# Leds.net
KiCad netlist of a schematic drawn in Altium Designer
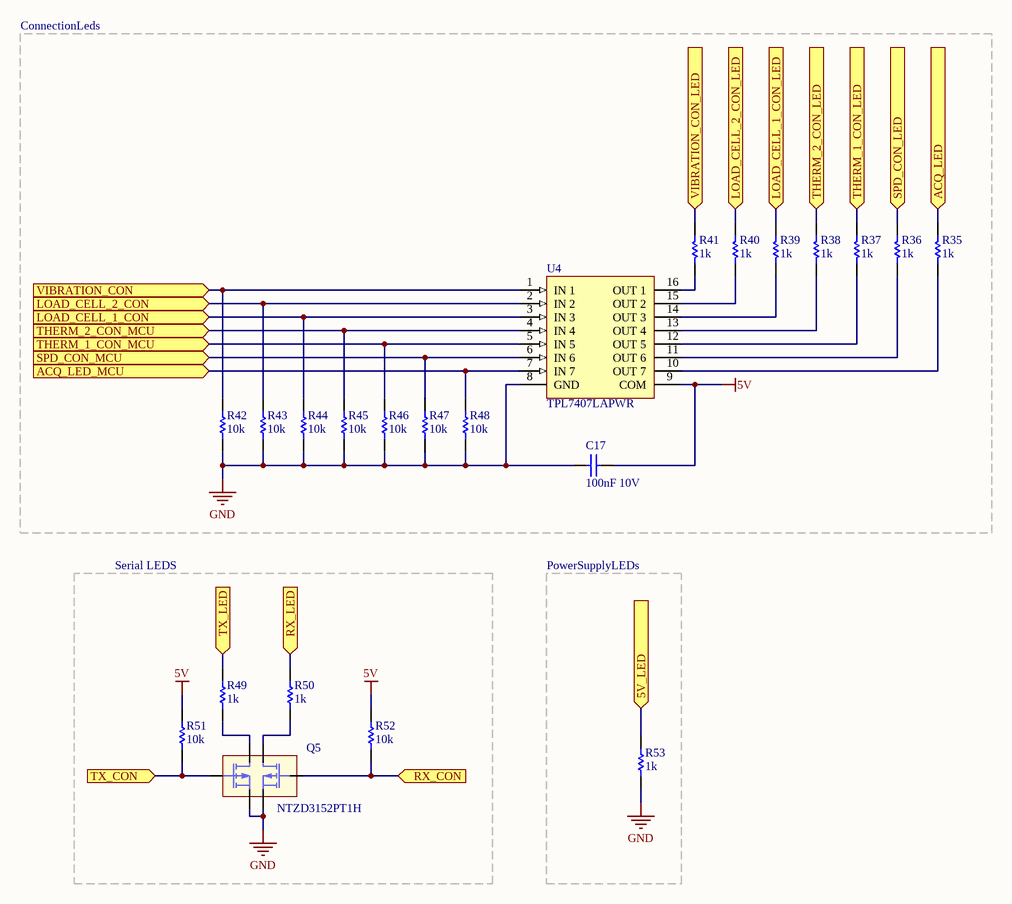
[diagram p0: Leds.SchDoc]

(export (version "E")
  (design (tool "Eeschema 10.0.6"))
  (components
    (comp (ref "C17")
      (value "100nF 10V")
      (footprint "0402")
      (description "Capacitor")
      (fields (field (name "PARTNUMBER") "CAP.100n.10V.20%.SMD.0402") (field (name "MANUFACTURER") "Wurth"))
      (libsource (lib "IntLib") (part "Cap"))
    )
    (comp (ref "Q5")
      (value "NTZD3152PT1H")
      (footprint "SOT23-6_M")
      (description "−20 V, −430 mA, Dual P−Channel with ESD Protection, SOT−563")
      (fields (field (name "PARTNUMBER") "NTZD315PT1H") (field (name "MANUFACTURER") "ON Semiconductor"))
      (libsource (lib "IntLib") (part "NTZD3152PT1H"))
    )
    (comp (ref "R35")
      (value "1k")
      (footprint "6-0805_M")
      (description "Resistor")
      (fields (field (name "PARTNUMBER") "RES.1K.1/8W.5%.SMD.0805") (field (name "MANUFACTURER") "Yageo"))
      (libsource (lib "IntLib") (part "Res"))
    )
    (comp (ref "R36")
      (value "1k")
      (footprint "6-0805_M")
      (description "Resistor")
      (fields (field (name "PARTNUMBER") "RES.1K.1/8W.5%.SMD.0805") (field (name "MANUFACTURER") "Yageo"))
      (libsource (lib "IntLib") (part "Res"))
    )
    (comp (ref "R37")
      (value "1k")
      (footprint "6-0805_M")
      (description "Resistor")
      (fields (field (name "PARTNUMBER") "RES.1K.1/8W.5%.SMD.0805") (field (name "MANUFACTURER") "Yageo"))
      (libsource (lib "IntLib") (part "Res"))
    )
    (comp (ref "R38")
      (value "1k")
      (footprint "6-0805_M")
      (description "Resistor")
      (fields (field (name "PARTNUMBER") "RES.1K.1/8W.5%.SMD.0805") (field (name "MANUFACTURER") "Yageo"))
      (libsource (lib "IntLib") (part "Res"))
    )
    (comp (ref "R39")
      (value "1k")
      (footprint "6-0805_M")
      (description "Resistor")
      (fields (field (name "PARTNUMBER") "RES.1K.1/8W.5%.SMD.0805") (field (name "MANUFACTURER") "Yageo"))
      (libsource (lib "IntLib") (part "Res"))
    )
    (comp (ref "R40")
      (value "1k")
      (footprint "6-0805_M")
      (description "Resistor")
      (fields (field (name "PARTNUMBER") "RES.1K.1/8W.5%.SMD.0805") (field (name "MANUFACTURER") "Yageo"))
      (libsource (lib "IntLib") (part "Res"))
    )
    (comp (ref "R41")
      (value "1k")
      (footprint "6-0805_M")
      (description "Resistor")
      (fields (field (name "PARTNUMBER") "RES.1K.1/8W.5%.SMD.0805") (field (name "MANUFACTURER") "Yageo"))
      (libsource (lib "IntLib") (part "Res"))
    )
    (comp (ref "R42")
      (value "10k")
      (footprint "6-0805_M")
      (description "Resistor")
      (fields (field (name "PARTNUMBER") "RES.10K.1/8W.5%.SMD.0805") (field (name "MANUFACTURER") "Yageo"))
      (libsource (lib "IntLib") (part "Res"))
    )
    (comp (ref "R43")
      (value "10k")
      (footprint "6-0805_M")
      (description "Resistor")
      (fields (field (name "PARTNUMBER") "RES.10K.1/8W.5%.SMD.0805") (field (name "MANUFACTURER") "Yageo"))
      (libsource (lib "IntLib") (part "Res"))
    )
    (comp (ref "R44")
      (value "10k")
      (footprint "6-0805_M")
      (description "Resistor")
      (fields (field (name "PARTNUMBER") "RES.10K.1/8W.5%.SMD.0805") (field (name "MANUFACTURER") "Yageo"))
      (libsource (lib "IntLib") (part "Res"))
    )
    (comp (ref "R45")
      (value "10k")
      (footprint "6-0805_M")
      (description "Resistor")
      (fields (field (name "PARTNUMBER") "RES.10K.1/8W.5%.SMD.0805") (field (name "MANUFACTURER") "Yageo"))
      (libsource (lib "IntLib") (part "Res"))
    )
    (comp (ref "R46")
      (value "10k")
      (footprint "6-0805_M")
      (description "Resistor")
      (fields (field (name "PARTNUMBER") "RES.10K.1/8W.5%.SMD.0805") (field (name "MANUFACTURER") "Yageo"))
      (libsource (lib "IntLib") (part "Res"))
    )
    (comp (ref "R47")
      (value "10k")
      (footprint "6-0805_M")
      (description "Resistor")
      (fields (field (name "PARTNUMBER") "RES.10K.1/8W.5%.SMD.0805") (field (name "MANUFACTURER") "Yageo"))
      (libsource (lib "IntLib") (part "Res"))
    )
    (comp (ref "R48")
      (value "10k")
      (footprint "6-0805_M")
      (description "Resistor")
      (fields (field (name "PARTNUMBER") "RES.10K.1/8W.5%.SMD.0805") (field (name "MANUFACTURER") "Yageo"))
      (libsource (lib "IntLib") (part "Res"))
    )
    (comp (ref "R49")
      (value "1k")
      (footprint "6-0805_M")
      (description "Resistor")
      (fields (field (name "PARTNUMBER") "RES.1K.1/8W.5%.SMD.0805") (field (name "MANUFACTURER") "Yageo"))
      (libsource (lib "IntLib") (part "Res"))
    )
    (comp (ref "R50")
      (value "1k")
      (footprint "6-0805_M")
      (description "Resistor")
      (fields (field (name "PARTNUMBER") "RES.1K.1/8W.5%.SMD.0805") (field (name "MANUFACTURER") "Yageo"))
      (libsource (lib "IntLib") (part "Res"))
    )
    (comp (ref "R51")
      (value "10k")
      (footprint "6-0805_M")
      (description "Resistor")
      (fields (field (name "PARTNUMBER") "RES.10K.1/8W.5%.SMD.0805") (field (name "MANUFACTURER") "Yageo"))
      (libsource (lib "IntLib") (part "Res"))
    )
    (comp (ref "R52")
      (value "10k")
      (footprint "6-0805_M")
      (description "Resistor")
      (fields (field (name "PARTNUMBER") "RES.10K.1/8W.5%.SMD.0805") (field (name "MANUFACTURER") "Yageo"))
      (libsource (lib "IntLib") (part "Res"))
    )
    (comp (ref "R53")
      (value "1k")
      (footprint "6-0805_M")
      (description "Resistor")
      (fields (field (name "PARTNUMBER") "RES.1K.1/8W.5%.SMD.0805") (field (name "MANUFACTURER") "Yageo"))
      (libsource (lib "IntLib") (part "Res"))
    )
    (comp (ref "U4")
      (value "TPL7407LAPWR")
      (footprint "TSOP-16")
      (fields (field (name "MANUFACTURER") "TL2575-05"))
      (libsource (lib "IntLib") (part "TPL7407LAPWR"))
    )
  )
  (nets
    (net (code "1") (name "/5V_LED") (class "Default")
      (node (ref "R53") (pin "2") (pinfunction "2_2") (pintype "passive"))
    )
    (net (code "2") (name "/ACQ_LED") (class "Default")
      (node (ref "R35") (pin "2") (pinfunction "2_2") (pintype "passive"))
    )
    (net (code "3") (name "/ACQ_LED_MCU") (class "Default")
      (node (ref "R48") (pin "2") (pinfunction "2_2") (pintype "passive"))
      (node (ref "U4") (pin "7") (pinfunction "IN_7_7") (pintype "input"))
    )
    (net (code "4") (name "/LOAD_CELL_1_CON") (class "Default")
      (node (ref "R44") (pin "2") (pinfunction "2_2") (pintype "passive"))
      (node (ref "U4") (pin "3") (pinfunction "IN_3_3") (pintype "input"))
    )
    (net (code "5") (name "/LOAD_CELL_1_CON_LED") (class "Default")
      (node (ref "R39") (pin "2") (pinfunction "2_2") (pintype "passive"))
    )
    (net (code "6") (name "/LOAD_CELL_2_CON") (class "Default")
      (node (ref "R43") (pin "2") (pinfunction "2_2") (pintype "passive"))
      (node (ref "U4") (pin "2") (pinfunction "IN_2_2") (pintype "input"))
    )
    (net (code "7") (name "/LOAD_CELL_2_CON_LED") (class "Default")
      (node (ref "R40") (pin "2") (pinfunction "2_2") (pintype "passive"))
    )
    (net (code "8") (name "/RX_CON") (class "Default")
      (node (ref "Q5") (pin "5") (pinfunction "G2_5") (pintype "passive"))
      (node (ref "R52") (pin "1") (pinfunction "1_1") (pintype "passive"))
    )
    (net (code "9") (name "/RX_LED") (class "Default")
      (node (ref "R50") (pin "2") (pinfunction "2_2") (pintype "passive"))
    )
    (net (code "10") (name "/SPD_CON_LED") (class "Default")
      (node (ref "R36") (pin "2") (pinfunction "2_2") (pintype "passive"))
    )
    (net (code "11") (name "/SPD_CON_MCU") (class "Default")
      (node (ref "R47") (pin "2") (pinfunction "2_2") (pintype "passive"))
      (node (ref "U4") (pin "6") (pinfunction "IN_6_6") (pintype "input"))
    )
    (net (code "12") (name "/THERM_1_CON_LED") (class "Default")
      (node (ref "R37") (pin "2") (pinfunction "2_2") (pintype "passive"))
    )
    (net (code "13") (name "/THERM_1_CON_MCU") (class "Default")
      (node (ref "R46") (pin "2") (pinfunction "2_2") (pintype "passive"))
      (node (ref "U4") (pin "5") (pinfunction "IN_5_5") (pintype "input"))
    )
    (net (code "14") (name "/THERM_2_CON_LED") (class "Default")
      (node (ref "R38") (pin "2") (pinfunction "2_2") (pintype "passive"))
    )
    (net (code "15") (name "/THERM_2_CON_MCU") (class "Default")
      (node (ref "R45") (pin "2") (pinfunction "2_2") (pintype "passive"))
      (node (ref "U4") (pin "4") (pinfunction "IN_4_4") (pintype "input"))
    )
    (net (code "16") (name "/TX_CON") (class "Default")
      (node (ref "Q5") (pin "2") (pinfunction "G1_2") (pintype "passive"))
      (node (ref "R51") (pin "1") (pinfunction "1_1") (pintype "passive"))
    )
    (net (code "17") (name "/TX_LED") (class "Default")
      (node (ref "R49") (pin "2") (pinfunction "2_2") (pintype "passive"))
    )
    (net (code "18") (name "/VIBRATION_CON") (class "Default")
      (node (ref "R42") (pin "2") (pinfunction "2_2") (pintype "passive"))
      (node (ref "U4") (pin "1") (pinfunction "IN_1_1") (pintype "input"))
    )
    (net (code "19") (name "/VIBRATION_CON_LED") (class "Default")
      (node (ref "R41") (pin "2") (pinfunction "2_2") (pintype "passive"))
    )
    (net (code "20") (name "5V") (class "Default")
      (node (ref "C17") (pin "2") (pinfunction "2_2") (pintype "passive"))
      (node (ref "R51") (pin "2") (pinfunction "2_2") (pintype "passive"))
      (node (ref "R52") (pin "2") (pinfunction "2_2") (pintype "passive"))
      (node (ref "U4") (pin "9") (pinfunction "COM_9") (pintype "power_in"))
    )
    (net (code "21") (name "GND") (class "Default")
      (node (ref "C17") (pin "1") (pinfunction "1_1") (pintype "passive"))
      (node (ref "Q5") (pin "1") (pinfunction "S1_1") (pintype "passive"))
      (node (ref "Q5") (pin "4") (pinfunction "S2_4") (pintype "passive"))
      (node (ref "R42") (pin "1") (pinfunction "1_1") (pintype "passive"))
      (node (ref "R43") (pin "1") (pinfunction "1_1") (pintype "passive"))
      (node (ref "R44") (pin "1") (pinfunction "1_1") (pintype "passive"))
      (node (ref "R45") (pin "1") (pinfunction "1_1") (pintype "passive"))
      (node (ref "R46") (pin "1") (pinfunction "1_1") (pintype "passive"))
      (node (ref "R47") (pin "1") (pinfunction "1_1") (pintype "passive"))
      (node (ref "R48") (pin "1") (pinfunction "1_1") (pintype "passive"))
      (node (ref "R53") (pin "1") (pinfunction "1_1") (pintype "passive"))
      (node (ref "U4") (pin "8") (pinfunction "GND_8") (pintype "power_in"))
    )
    (net (code "22") (name "Net-(Q5-D1)") (class "Default")
      (node (ref "Q5") (pin "6") (pinfunction "D1_6") (pintype "passive"))
      (node (ref "R49") (pin "1") (pinfunction "1_1") (pintype "passive"))
    )
    (net (code "23") (name "Net-(Q5-D2)") (class "Default")
      (node (ref "Q5") (pin "3") (pinfunction "D2_3") (pintype "passive"))
      (node (ref "R50") (pin "1") (pinfunction "1_1") (pintype "passive"))
    )
    (net (code "24") (name "Net-(U4-OUT_1)") (class "Default")
      (node (ref "R41") (pin "1") (pinfunction "1_1") (pintype "passive"))
      (node (ref "U4") (pin "16") (pinfunction "OUT_1_16") (pintype "passive"))
    )
    (net (code "25") (name "Net-(U4-OUT_2)") (class "Default")
      (node (ref "R40") (pin "1") (pinfunction "1_1") (pintype "passive"))
      (node (ref "U4") (pin "15") (pinfunction "OUT_2_15") (pintype "passive"))
    )
    (net (code "26") (name "Net-(U4-OUT_3)") (class "Default")
      (node (ref "R39") (pin "1") (pinfunction "1_1") (pintype "passive"))
      (node (ref "U4") (pin "14") (pinfunction "OUT_3_14") (pintype "passive"))
    )
    (net (code "27") (name "Net-(U4-OUT_4)") (class "Default")
      (node (ref "R38") (pin "1") (pinfunction "1_1") (pintype "passive"))
      (node (ref "U4") (pin "13") (pinfunction "OUT_4_13") (pintype "passive"))
    )
    (net (code "28") (name "Net-(U4-OUT_5)") (class "Default")
      (node (ref "R37") (pin "1") (pinfunction "1_1") (pintype "passive"))
      (node (ref "U4") (pin "12") (pinfunction "OUT_5_12") (pintype "passive"))
    )
    (net (code "29") (name "Net-(U4-OUT_6)") (class "Default")
      (node (ref "R36") (pin "1") (pinfunction "1_1") (pintype "passive"))
      (node (ref "U4") (pin "11") (pinfunction "OUT_6_11") (pintype "passive"))
    )
    (net (code "30") (name "Net-(U4-OUT_7)") (class "Default")
      (node (ref "R35") (pin "1") (pinfunction "1_1") (pintype "passive"))
      (node (ref "U4") (pin "10") (pinfunction "OUT_7_10") (pintype "passive"))
    )
  )
)
